# Arduino_Electronic_Load_Ver06.net
KiCad netlist of a schematic drawn in EAGLE
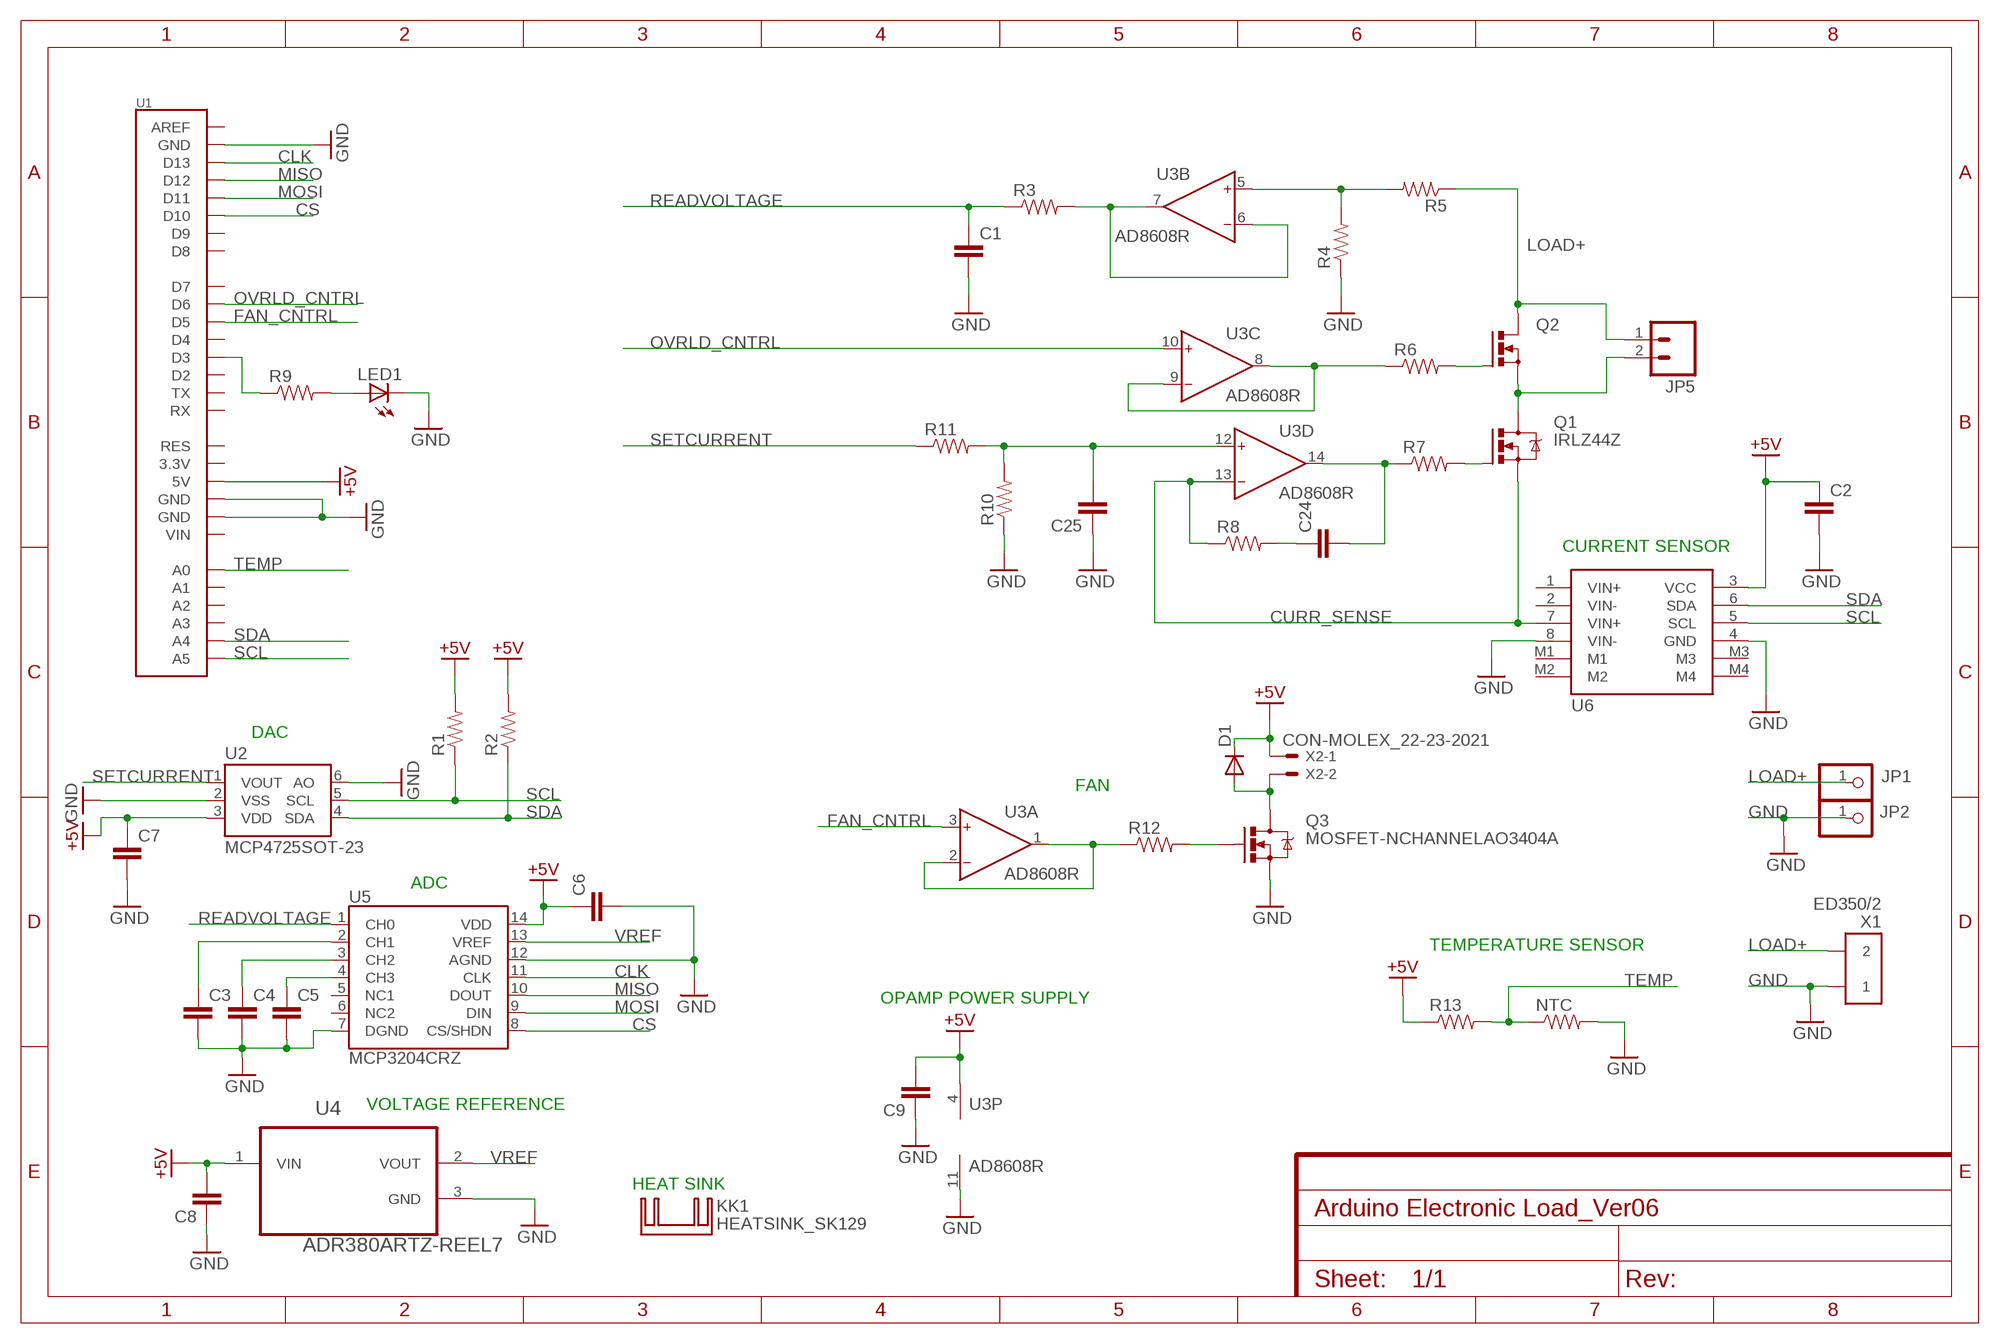
[diagram p0: schematic, sheet 1]

(export (version "E")
  (design (tool "Eeschema 10.0.6"))
  (components
    (comp (ref "C1")
      (value "CAP0603-CAP")
      (footprint "eagle-import:0603-CAP")
      (fields (field (name "VENDOR_PART_NUM") "Digikey"))
      (libsource (lib "eagle-import") (part "CAP0603-CAP"))
    )
    (comp (ref "C2")
      (value "CAP0603-CAP")
      (footprint "eagle-import:0603-CAP")
      (fields (field (name "VENDOR_PART_NUM") "Digikey"))
      (libsource (lib "eagle-import") (part "CAP0603-CAP"))
    )
    (comp (ref "C3")
      (value "CAP0603-CAP")
      (footprint "eagle-import:0603-CAP")
      (fields (field (name "VENDOR_PART_NUM") "Digikey"))
      (libsource (lib "eagle-import") (part "CAP0603-CAP"))
    )
    (comp (ref "C4")
      (value "CAP0603-CAP")
      (footprint "eagle-import:0603-CAP")
      (fields (field (name "VENDOR_PART_NUM") "Digikey"))
      (libsource (lib "eagle-import") (part "CAP0603-CAP"))
    )
    (comp (ref "C5")
      (value "CAP0603-CAP")
      (footprint "eagle-import:0603-CAP")
      (fields (field (name "VENDOR_PART_NUM") "Digikey"))
      (libsource (lib "eagle-import") (part "CAP0603-CAP"))
    )
    (comp (ref "C6")
      (value "CAP0603-CAP")
      (footprint "eagle-import:0603-CAP")
      (libsource (lib "eagle-import") (part "CAP0603-CAP"))
    )
    (comp (ref "C7")
      (value "CAP0603-CAP")
      (footprint "eagle-import:0603-CAP")
      (libsource (lib "eagle-import") (part "CAP0603-CAP"))
    )
    (comp (ref "C8")
      (value "CAP0603-CAP")
      (footprint "eagle-import:0603-CAP")
      (libsource (lib "eagle-import") (part "CAP0603-CAP"))
    )
    (comp (ref "C9")
      (value "CAP0603-CAP")
      (footprint "eagle-import:0603-CAP")
      (libsource (lib "eagle-import") (part "CAP0603-CAP"))
    )
    (comp (ref "C24")
      (value "CAP0603-CAP")
      (footprint "eagle-import:0603-CAP")
      (libsource (lib "eagle-import") (part "CAP0603-CAP"))
    )
    (comp (ref "C25")
      (value "CAP0603-CAP")
      (footprint "eagle-import:0603-CAP")
      (libsource (lib "eagle-import") (part "CAP0603-CAP"))
    )
    (comp (ref "D1")
      (value "DIODEPTH")
      (footprint "eagle-import:DIODE-1N4001")
      (libsource (lib "eagle-import") (part "DIODEPTH"))
    )
    (comp (ref "JP1")
      (value "PINHEAD_PINHD-1X1")
      (footprint "eagle-import:PINHEAD_1X01")
      (libsource (lib "eagle-import") (part "PINHEAD_PINHD-1X1"))
    )
    (comp (ref "JP2")
      (value "PINHEAD_PINHD-1X1")
      (footprint "eagle-import:PINHEAD_1X01")
      (libsource (lib "eagle-import") (part "PINHEAD_PINHD-1X1"))
    )
    (comp (ref "JP5")
      (value "M02")
      (footprint "eagle-import:1X02_LONGPADS")
      (libsource (lib "eagle-import") (part "M02"))
    )
    (comp (ref "KK1")
      (value "HEATSINK_SK129")
      (footprint "eagle-import:HEATSINK_SK129-HOLE")
      (libsource (lib "eagle-import") (part "HEATSINK_SK129"))
    )
    (comp (ref "LED1")
      (value "LED5MM")
      (footprint "eagle-import:LED5MM")
      (libsource (lib "eagle-import") (part "LED5MM"))
    )
    (comp (ref "NTC")
      (value "RESISTOR0402-RES")
      (footprint "eagle-import:0402-RES")
      (libsource (lib "eagle-import") (part "RESISTOR0402-RES"))
    )
    (comp (ref "Q1")
      (value "IRLZ44Z")
      (footprint "eagle-import:TO220BV_1")
      (libsource (lib "eagle-import") (part "IRLZ44Z"))
    )
    (comp (ref "Q2")
      (value "PMOSFET_NTO220BV")
      (footprint "eagle-import:TO220BV")
      (libsource (lib "eagle-import") (part "PMOSFET_NTO220BV"))
    )
    (comp (ref "Q3")
      (value "MOSFET-NCHANNELAO3404A")
      (footprint "eagle-import:SOT23-3")
      (libsource (lib "eagle-import") (part "MOSFET-NCHANNELAO3404A"))
    )
    (comp (ref "R1")
      (value "RESISTOR0603-RES")
      (footprint "eagle-import:0603-RES")
      (libsource (lib "eagle-import") (part "RESISTOR0603-RES"))
    )
    (comp (ref "R2")
      (value "RESISTOR0603-RES")
      (footprint "eagle-import:0603-RES")
      (libsource (lib "eagle-import") (part "RESISTOR0603-RES"))
    )
    (comp (ref "R3")
      (value "RESISTOR0603-RES")
      (footprint "eagle-import:0603-RES")
      (libsource (lib "eagle-import") (part "RESISTOR0603-RES"))
    )
    (comp (ref "R4")
      (value "RESISTOR0603-RES")
      (footprint "eagle-import:0603-RES")
      (libsource (lib "eagle-import") (part "RESISTOR0603-RES"))
    )
    (comp (ref "R5")
      (value "RESISTOR0603-RES")
      (footprint "eagle-import:0603-RES")
      (libsource (lib "eagle-import") (part "RESISTOR0603-RES"))
    )
    (comp (ref "R6")
      (value "RESISTOR0603-RES")
      (footprint "eagle-import:0603-RES")
      (libsource (lib "eagle-import") (part "RESISTOR0603-RES"))
    )
    (comp (ref "R7")
      (value "RESISTOR0603-RES")
      (footprint "eagle-import:0603-RES")
      (libsource (lib "eagle-import") (part "RESISTOR0603-RES"))
    )
    (comp (ref "R8")
      (value "RESISTOR0603-RES")
      (footprint "eagle-import:0603-RES")
      (libsource (lib "eagle-import") (part "RESISTOR0603-RES"))
    )
    (comp (ref "R9")
      (value "RESISTOR0603-RES")
      (footprint "eagle-import:0603-RES")
      (libsource (lib "eagle-import") (part "RESISTOR0603-RES"))
    )
    (comp (ref "R10")
      (value "RESISTOR0603-RES")
      (footprint "eagle-import:0603-RES")
      (libsource (lib "eagle-import") (part "RESISTOR0603-RES"))
    )
    (comp (ref "R11")
      (value "RESISTOR0603-RES")
      (footprint "eagle-import:0603-RES")
      (libsource (lib "eagle-import") (part "RESISTOR0603-RES"))
    )
    (comp (ref "R12")
      (value "RESISTOR0603-RES")
      (footprint "eagle-import:0603-RES")
      (libsource (lib "eagle-import") (part "RESISTOR0603-RES"))
    )
    (comp (ref "R13")
      (value "RESISTOR0603-RES")
      (footprint "eagle-import:0603-RES")
      (libsource (lib "eagle-import") (part "RESISTOR0603-RES"))
    )
    (comp (ref "U1")
      (value "ARDUINO_SHIELD")
      (footprint "eagle-import:DUEMILANOVE_SHIELD")
      (libsource (lib "eagle-import") (part "ARDUINO_SHIELD"))
    )
    (comp (ref "U2")
      (value "MCP4725SOT-23")
      (footprint "eagle-import:SOT23-6")
      (libsource (lib "eagle-import") (part "MCP4725SOT-23"))
    )
    (comp (ref "U3")
      (value "AD8608R")
      (footprint "eagle-import:SO14")
      (libsource (lib "eagle-import") (part "AD8608R"))
    )
    (comp (ref "U4")
      (value "ADR380ARTZ-REEL7")
      (footprint "eagle-import:SOT95P237X112-3N")
      (libsource (lib "eagle-import") (part "ADR380ARTZ-REEL7"))
    )
    (comp (ref "U5")
      (value "MCP3204CRZ")
      (footprint "eagle-import:SOIC-14")
      (libsource (lib "eagle-import") (part "MCP3204CRZ"))
    )
    (comp (ref "U6")
      (value "INA219")
      (footprint "eagle-import:INA219")
      (libsource (lib "eagle-import") (part "INA219"))
    )
    (comp (ref "X1")
      (value "ED350/2")
      (footprint "eagle-import:ED350_2")
      (libsource (lib "eagle-import") (part "ED350/2"))
    )
    (comp (ref "X2")
      (value "CON-MOLEX_22-23-2021")
      (footprint "eagle-import:CON-MOLEX_22-23-2021")
      (libsource (lib "eagle-import") (part "CON-MOLEX_22-23-2021"))
    )
  )
  (nets
    (net (code "1") (name "+5V") (class "Default")
      (node (ref "C2") (pin "1") (pinfunction "1_1") (pintype "passive"))
      (node (ref "C6") (pin "1") (pinfunction "1_1") (pintype "passive"))
      (node (ref "C7") (pin "1") (pinfunction "1_1") (pintype "passive"))
      (node (ref "C8") (pin "2") (pinfunction "2_2") (pintype "passive"))
      (node (ref "C9") (pin "2") (pinfunction "2_2") (pintype "passive"))
      (node (ref "D1") (pin "C") (pinfunction "C_C") (pintype "passive"))
      (node (ref "R1") (pin "2") (pinfunction "2_2") (pintype "passive"))
      (node (ref "R13") (pin "1") (pinfunction "1_1") (pintype "passive"))
      (node (ref "R2") (pin "2") (pinfunction "2_2") (pintype "passive"))
      (node (ref "U1") (pin "5V") (pinfunction "5V_5V") (pintype "bidirectional"))
      (node (ref "U2") (pin "3") (pinfunction "VDD_3") (pintype "bidirectional"))
      (node (ref "U3") (pin "4") (pinfunction "V+_4") (pintype "power_in"))
      (node (ref "U4") (pin "1") (pinfunction "VIN_1") (pintype "passive"))
      (node (ref "U5") (pin "14") (pinfunction "VDD_14") (pintype "bidirectional"))
      (node (ref "U6") (pin "3") (pinfunction "VCC_3") (pintype "bidirectional"))
      (node (ref "X2") (pin "1") (pinfunction "S_1") (pintype "passive"))
    )
    (net (code "2") (name "/CLK") (class "Default")
      (node (ref "U1") (pin "D13") (pinfunction "D13_D13") (pintype "bidirectional"))
      (node (ref "U5") (pin "11") (pinfunction "CLK_11") (pintype "bidirectional"))
    )
    (net (code "3") (name "/CS") (class "Default")
      (node (ref "U1") (pin "D10") (pinfunction "D10_D10") (pintype "bidirectional"))
      (node (ref "U5") (pin "8") (pinfunction "CS/SHDN_8") (pintype "bidirectional"))
    )
    (net (code "4") (name "/CURR_SENSE") (class "Default")
      (node (ref "Q1") (pin "S") (pinfunction "S_S") (pintype "passive"))
      (node (ref "R8") (pin "1") (pinfunction "1_1") (pintype "passive"))
      (node (ref "U3") (pin "13") (pinfunction "IN-_13") (pintype "input"))
      (node (ref "U6") (pin "7") (pinfunction "VIN+_7") (pintype "bidirectional"))
    )
    (net (code "5") (name "/FAN_CNTRL") (class "Default")
      (node (ref "U1") (pin "D5") (pinfunction "D5_D5") (pintype "bidirectional"))
      (node (ref "U3") (pin "3") (pinfunction "IN+_3") (pintype "input"))
    )
    (net (code "6") (name "/LOAD+") (class "Default")
      (node (ref "JP1") (pin "1") (pinfunction "1_1") (pintype "passive"))
      (node (ref "JP5") (pin "1") (pinfunction "1_1") (pintype "passive"))
      (node (ref "Q2") (pin "D") (pinfunction "D_D") (pintype "passive"))
      (node (ref "R5") (pin "1") (pinfunction "1_1") (pintype "passive"))
      (node (ref "X1") (pin "P$2") (pinfunction "2_P$2") (pintype "bidirectional"))
    )
    (net (code "7") (name "/MISO") (class "Default")
      (node (ref "U1") (pin "D12") (pinfunction "D12_D12") (pintype "bidirectional"))
      (node (ref "U5") (pin "10") (pinfunction "DOUT_10") (pintype "bidirectional"))
    )
    (net (code "8") (name "/MOSI") (class "Default")
      (node (ref "U1") (pin "D11") (pinfunction "D11_D11") (pintype "bidirectional"))
      (node (ref "U5") (pin "9") (pinfunction "DIN_9") (pintype "bidirectional"))
    )
    (net (code "9") (name "/OVRLD_CNTRL") (class "Default")
      (node (ref "U1") (pin "D6") (pinfunction "D6_D6") (pintype "bidirectional"))
      (node (ref "U3") (pin "10") (pinfunction "IN+_10") (pintype "input"))
    )
    (net (code "10") (name "/READVOLTAGE") (class "Default")
      (node (ref "C1") (pin "1") (pinfunction "1_1") (pintype "passive"))
      (node (ref "R3") (pin "1") (pinfunction "1_1") (pintype "passive"))
      (node (ref "U5") (pin "1") (pinfunction "CH0_1") (pintype "bidirectional"))
    )
    (net (code "11") (name "/SCL") (class "Default")
      (node (ref "R1") (pin "1") (pinfunction "1_1") (pintype "passive"))
      (node (ref "U1") (pin "A5") (pinfunction "A5_A5") (pintype "bidirectional"))
      (node (ref "U2") (pin "5") (pinfunction "SCL_5") (pintype "bidirectional"))
      (node (ref "U6") (pin "5") (pinfunction "SCL_5") (pintype "bidirectional"))
    )
    (net (code "12") (name "/SDA") (class "Default")
      (node (ref "R2") (pin "1") (pinfunction "1_1") (pintype "passive"))
      (node (ref "U1") (pin "A4") (pinfunction "A4_A4") (pintype "bidirectional"))
      (node (ref "U2") (pin "4") (pinfunction "SDA_4") (pintype "bidirectional"))
      (node (ref "U6") (pin "6") (pinfunction "SDA_6") (pintype "bidirectional"))
    )
    (net (code "13") (name "/SETCURRENT") (class "Default")
      (node (ref "R11") (pin "1") (pinfunction "1_1") (pintype "passive"))
      (node (ref "U2") (pin "1") (pinfunction "VOUT_1") (pintype "bidirectional"))
    )
    (net (code "14") (name "/TEMP") (class "Default")
      (node (ref "NTC") (pin "1") (pinfunction "1_1") (pintype "passive"))
      (node (ref "R13") (pin "2") (pinfunction "2_2") (pintype "passive"))
      (node (ref "U1") (pin "A0") (pinfunction "A0_A0") (pintype "bidirectional"))
    )
    (net (code "15") (name "/VREF") (class "Default")
      (node (ref "U4") (pin "2") (pinfunction "VOUT_2") (pintype "passive"))
      (node (ref "U5") (pin "13") (pinfunction "VREF_13") (pintype "bidirectional"))
    )
    (net (code "16") (name "GND") (class "Default")
      (node (ref "C1") (pin "2") (pinfunction "2_2") (pintype "passive"))
      (node (ref "C2") (pin "2") (pinfunction "2_2") (pintype "passive"))
      (node (ref "C25") (pin "1") (pinfunction "1_1") (pintype "passive"))
      (node (ref "C3") (pin "2") (pinfunction "2_2") (pintype "passive"))
      (node (ref "C4") (pin "2") (pinfunction "2_2") (pintype "passive"))
      (node (ref "C5") (pin "2") (pinfunction "2_2") (pintype "passive"))
      (node (ref "C6") (pin "2") (pinfunction "2_2") (pintype "passive"))
      (node (ref "C7") (pin "2") (pinfunction "2_2") (pintype "passive"))
      (node (ref "C8") (pin "1") (pinfunction "1_1") (pintype "passive"))
      (node (ref "C9") (pin "1") (pinfunction "1_1") (pintype "passive"))
      (node (ref "JP2") (pin "1") (pinfunction "1_1") (pintype "passive"))
      (node (ref "LED1") (pin "K") (pinfunction "C_K") (pintype "passive"))
      (node (ref "NTC") (pin "2") (pinfunction "2_2") (pintype "passive"))
      (node (ref "Q3") (pin "2") (pinfunction "S_2") (pintype "passive"))
      (node (ref "R10") (pin "1") (pinfunction "1_1") (pintype "passive"))
      (node (ref "R4") (pin "1") (pinfunction "1_1") (pintype "passive"))
      (node (ref "U1") (pin "GND@0") (pinfunction "GND_GND@0") (pintype "bidirectional"))
      (node (ref "U1") (pin "GND@1") (pinfunction "GND_GND@1") (pintype "bidirectional"))
      (node (ref "U1") (pin "GND@2") (pinfunction "GND_GND@2") (pintype "bidirectional"))
      (node (ref "U2") (pin "2") (pinfunction "VSS_2") (pintype "bidirectional"))
      (node (ref "U2") (pin "6") (pinfunction "AO_6") (pintype "bidirectional"))
      (node (ref "U3") (pin "11") (pinfunction "V-_11") (pintype "power_in"))
      (node (ref "U4") (pin "3") (pinfunction "GND_3") (pintype "passive"))
      (node (ref "U5") (pin "12") (pinfunction "AGND_12") (pintype "bidirectional"))
      (node (ref "U5") (pin "7") (pinfunction "DGND_7") (pintype "bidirectional"))
      (node (ref "U6") (pin "4") (pinfunction "GND_4") (pintype "bidirectional"))
      (node (ref "U6") (pin "8") (pinfunction "VIN-_8") (pintype "bidirectional"))
      (node (ref "X1") (pin "P$1") (pinfunction "1_P$1") (pintype "bidirectional"))
    )
    (net (code "17") (name "Net-(C24-Pad1)") (class "Default")
      (node (ref "C24") (pin "1") (pinfunction "1_1") (pintype "passive"))
      (node (ref "R8") (pin "2") (pinfunction "2_2") (pintype "passive"))
    )
    (net (code "18") (name "Net-(JP5-Pad2)") (class "Default")
      (node (ref "JP5") (pin "2") (pinfunction "2_2") (pintype "passive"))
      (node (ref "Q1") (pin "D") (pinfunction "D_D") (pintype "passive"))
      (node (ref "Q2") (pin "S") (pinfunction "S_S") (pintype "passive"))
    )
    (net (code "19") (name "Net-(LED1-PadA)") (class "Default")
      (node (ref "LED1") (pin "A") (pinfunction "A_A") (pintype "passive"))
      (node (ref "R9") (pin "2") (pinfunction "2_2") (pintype "passive"))
    )
    (net (code "20") (name "Net-(Q1-PadG)") (class "Default")
      (node (ref "Q1") (pin "G") (pinfunction "G_G") (pintype "passive"))
      (node (ref "R7") (pin "2") (pinfunction "2_2") (pintype "passive"))
    )
    (net (code "21") (name "Net-(Q2-PadG)") (class "Default")
      (node (ref "Q2") (pin "G") (pinfunction "G_G") (pintype "passive"))
      (node (ref "R6") (pin "2") (pinfunction "2_2") (pintype "passive"))
    )
    (net (code "22") (name "Net-(Q3-D)") (class "Default")
      (node (ref "D1") (pin "A") (pinfunction "A_A") (pintype "passive"))
      (node (ref "Q3") (pin "3") (pinfunction "D_3") (pintype "passive"))
      (node (ref "X2") (pin "2") (pinfunction "S_2") (pintype "passive"))
    )
    (net (code "23") (name "Net-(Q3-G)") (class "Default")
      (node (ref "Q3") (pin "1") (pinfunction "G_1") (pintype "passive"))
      (node (ref "R12") (pin "2") (pinfunction "2_2") (pintype "passive"))
    )
    (net (code "24") (name "Net-(R9-Pad1)") (class "Default")
      (node (ref "R9") (pin "1") (pinfunction "1_1") (pintype "passive"))
      (node (ref "U1") (pin "D3") (pinfunction "D3_D3") (pintype "bidirectional"))
    )
    (net (code "25") (name "Net-(U3A-IN-)") (class "Default")
      (node (ref "R12") (pin "1") (pinfunction "1_1") (pintype "passive"))
      (node (ref "U3") (pin "1") (pinfunction "OUT_1") (pintype "output"))
      (node (ref "U3") (pin "2") (pinfunction "IN-_2") (pintype "input"))
    )
    (net (code "26") (name "Net-(U3B-IN+)") (class "Default")
      (node (ref "R4") (pin "2") (pinfunction "2_2") (pintype "passive"))
      (node (ref "R5") (pin "2") (pinfunction "2_2") (pintype "passive"))
      (node (ref "U3") (pin "5") (pinfunction "IN+_5") (pintype "input"))
    )
    (net (code "27") (name "Net-(U3B-IN-)") (class "Default")
      (node (ref "R3") (pin "2") (pinfunction "2_2") (pintype "passive"))
      (node (ref "U3") (pin "6") (pinfunction "IN-_6") (pintype "input"))
      (node (ref "U3") (pin "7") (pinfunction "OUT_7") (pintype "output"))
    )
    (net (code "28") (name "Net-(U3C-IN-)") (class "Default")
      (node (ref "R6") (pin "1") (pinfunction "1_1") (pintype "passive"))
      (node (ref "U3") (pin "8") (pinfunction "OUT_8") (pintype "output"))
      (node (ref "U3") (pin "9") (pinfunction "IN-_9") (pintype "input"))
    )
    (net (code "29") (name "Net-(U3D-IN+)") (class "Default")
      (node (ref "C25") (pin "2") (pinfunction "2_2") (pintype "passive"))
      (node (ref "R10") (pin "2") (pinfunction "2_2") (pintype "passive"))
      (node (ref "R11") (pin "2") (pinfunction "2_2") (pintype "passive"))
      (node (ref "U3") (pin "12") (pinfunction "IN+_12") (pintype "input"))
    )
    (net (code "30") (name "Net-(U3D-OUT)") (class "Default")
      (node (ref "C24") (pin "2") (pinfunction "2_2") (pintype "passive"))
      (node (ref "R7") (pin "1") (pinfunction "1_1") (pintype "passive"))
      (node (ref "U3") (pin "14") (pinfunction "OUT_14") (pintype "output"))
    )
    (net (code "31") (name "Net-(U5-CH1)") (class "Default")
      (node (ref "C3") (pin "1") (pinfunction "1_1") (pintype "passive"))
      (node (ref "U5") (pin "2") (pinfunction "CH1_2") (pintype "bidirectional"))
    )
    (net (code "32") (name "Net-(U5-CH2)") (class "Default")
      (node (ref "C4") (pin "1") (pinfunction "1_1") (pintype "passive"))
      (node (ref "U5") (pin "3") (pinfunction "CH2_3") (pintype "bidirectional"))
    )
    (net (code "33") (name "Net-(U5-CH3)") (class "Default")
      (node (ref "C5") (pin "1") (pinfunction "1_1") (pintype "passive"))
      (node (ref "U5") (pin "4") (pinfunction "CH3_4") (pintype "bidirectional"))
    )
    (net (code "34") (name "unconnected-(U1-Pad3.3V)") (class "Default")
      (node (ref "U1") (pin "3.3V") (pinfunction "3.3V_3.3V") (pintype "bidirectional"))
    )
    (net (code "35") (name "unconnected-(U1-PadA1)") (class "Default")
      (node (ref "U1") (pin "A1") (pinfunction "A1_A1") (pintype "bidirectional"))
    )
    (net (code "36") (name "unconnected-(U1-PadA2)") (class "Default")
      (node (ref "U1") (pin "A2") (pinfunction "A2_A2") (pintype "bidirectional"))
    )
    (net (code "37") (name "unconnected-(U1-PadA3)") (class "Default")
      (node (ref "U1") (pin "A3") (pinfunction "A3_A3") (pintype "bidirectional"))
    )
    (net (code "38") (name "unconnected-(U1-PadAREF)") (class "Default")
      (node (ref "U1") (pin "AREF") (pinfunction "AREF_AREF") (pintype "bidirectional"))
    )
    (net (code "39") (name "unconnected-(U1-PadD2)") (class "Default")
      (node (ref "U1") (pin "D2") (pinfunction "D2_D2") (pintype "bidirectional"))
    )
    (net (code "40") (name "unconnected-(U1-PadD4)") (class "Default")
      (node (ref "U1") (pin "D4") (pinfunction "D4_D4") (pintype "bidirectional"))
    )
    (net (code "41") (name "unconnected-(U1-PadD7)") (class "Default")
      (node (ref "U1") (pin "D7") (pinfunction "D7_D7") (pintype "bidirectional"))
    )
    (net (code "42") (name "unconnected-(U1-PadD8)") (class "Default")
      (node (ref "U1") (pin "D8") (pinfunction "D8_D8") (pintype "bidirectional"))
    )
    (net (code "43") (name "unconnected-(U1-PadD9)") (class "Default")
      (node (ref "U1") (pin "D9") (pinfunction "D9_D9") (pintype "bidirectional"))
    )
    (net (code "44") (name "unconnected-(U1-PadRES)") (class "Default")
      (node (ref "U1") (pin "RES") (pinfunction "RES_RES") (pintype "bidirectional"))
    )
    (net (code "45") (name "unconnected-(U1-PadRX)") (class "Default")
      (node (ref "U1") (pin "RX") (pinfunction "RX_RX") (pintype "bidirectional"))
    )
    (net (code "46") (name "unconnected-(U1-PadTX)") (class "Default")
      (node (ref "U1") (pin "TX") (pinfunction "TX_TX") (pintype "bidirectional"))
    )
    (net (code "47") (name "unconnected-(U1-PadVIN)") (class "Default")
      (node (ref "U1") (pin "VIN") (pinfunction "VIN_VIN") (pintype "bidirectional"))
    )
    (net (code "48") (name "unconnected-(U5-NC1-Pad5)") (class "Default")
      (node (ref "U5") (pin "5") (pinfunction "NC1_5") (pintype "bidirectional"))
    )
    (net (code "49") (name "unconnected-(U5-NC2-Pad6)") (class "Default")
      (node (ref "U5") (pin "6") (pinfunction "NC2_6") (pintype "bidirectional"))
    )
    (net (code "50") (name "unconnected-(U6-PadM1)") (class "Default")
      (node (ref "U6") (pin "M1") (pinfunction "M1_M1") (pintype "bidirectional"))
    )
    (net (code "51") (name "unconnected-(U6-PadM2)") (class "Default")
      (node (ref "U6") (pin "M2") (pinfunction "M2_M2") (pintype "bidirectional"))
    )
    (net (code "52") (name "unconnected-(U6-PadM3)") (class "Default")
      (node (ref "U6") (pin "M3") (pinfunction "M3_M3") (pintype "bidirectional"))
    )
    (net (code "53") (name "unconnected-(U6-PadM4)") (class "Default")
      (node (ref "U6") (pin "M4") (pinfunction "M4_M4") (pintype "bidirectional"))
    )
    (net (code "54") (name "unconnected-(U6-VIN+-Pad1)") (class "Default")
      (node (ref "U6") (pin "1") (pinfunction "VIN+_1") (pintype "bidirectional"))
    )
    (net (code "55") (name "unconnected-(U6-VIN--Pad2)") (class "Default")
      (node (ref "U6") (pin "2") (pinfunction "VIN-_2") (pintype "bidirectional"))
    )
  )
)
